# quadripod_2lm_nano.net
KiCad netlist of a schematic drawn in EAGLE
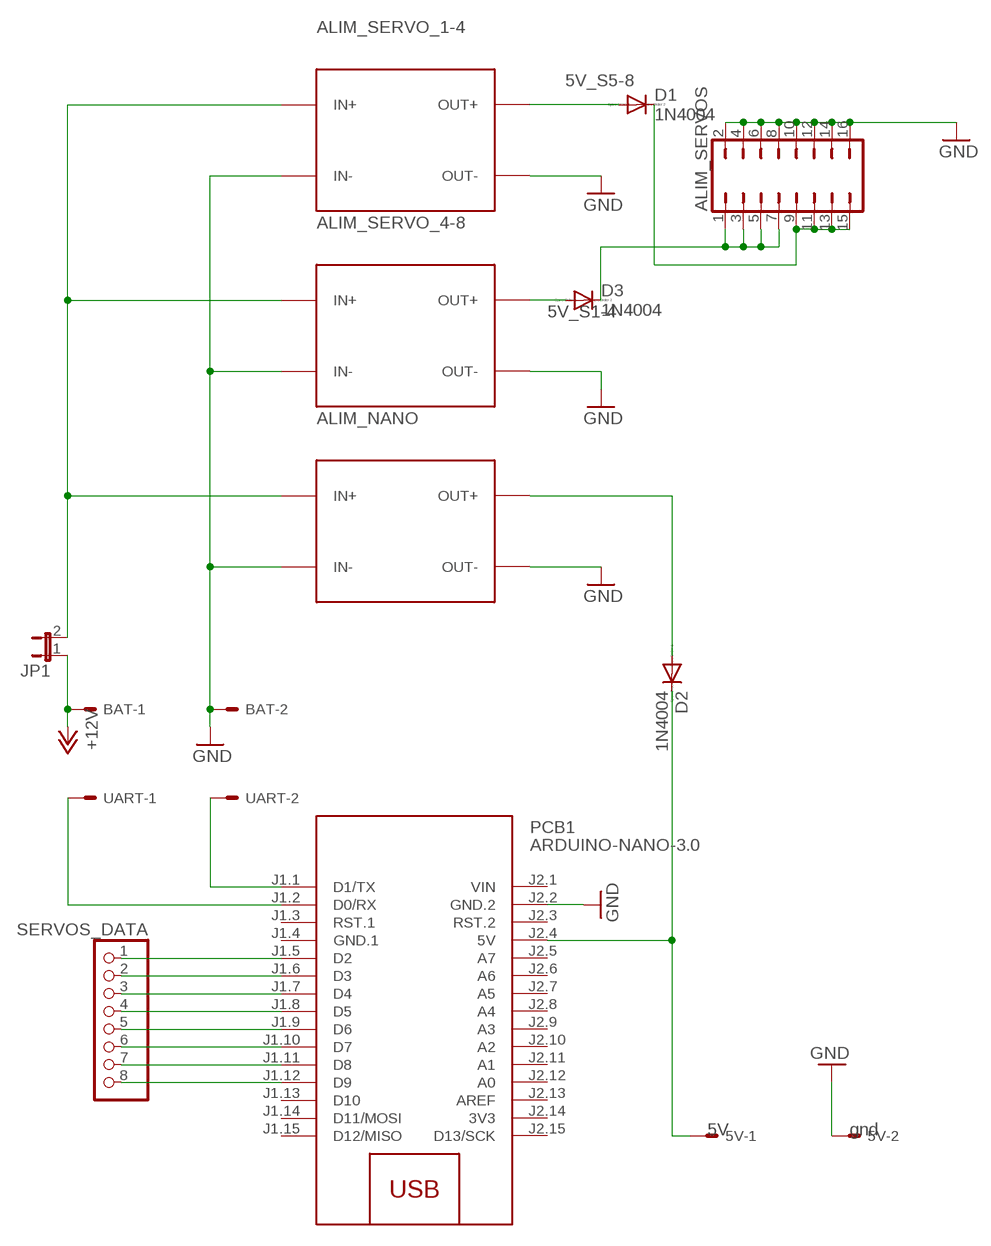
[diagram p0: schematic, sheet 1]

(export (version "E")
  (design (tool "Eeschema 10.0.6"))
  (components
    (comp (ref "5V")
      (value "332-02")
      (footprint "eagle-import:332-02")
      (fields (field (name "V") "5V") (field (name "VOLT") "gnd"))
      (libsource (lib "eagle-import") (part "332-02"))
    )
    (comp (ref "ALIM_NANO")
      (value "DC-DC-STEP-DOWN-LM2596")
      (footprint "eagle-import:DC-DC-STEP-DOWN-LM2596")
      (libsource (lib "eagle-import") (part "DC-DC-STEP-DOWN-LM2596"))
    )
    (comp (ref "ALIM_SERVOS")
      (value "JP8Q")
      (footprint "eagle-import:JP8Q")
      (libsource (lib "eagle-import") (part "JP8Q"))
    )
    (comp (ref "ALIM_SERVO_1-4")
      (value "DC-DC-STEP-DOWN-LM2596")
      (footprint "eagle-import:DC-DC-STEP-DOWN-LM2596")
      (libsource (lib "eagle-import") (part "DC-DC-STEP-DOWN-LM2596"))
    )
    (comp (ref "ALIM_SERVO_4-8")
      (value "DC-DC-STEP-DOWN-LM2596")
      (footprint "eagle-import:DC-DC-STEP-DOWN-LM2596")
      (libsource (lib "eagle-import") (part "DC-DC-STEP-DOWN-LM2596"))
    )
    (comp (ref "BAT")
      (value "332-02")
      (footprint "eagle-import:332-02")
      (fields (field (name "VOLTAGE") "12V") (field (name "VOLT") "gnd"))
      (libsource (lib "eagle-import") (part "332-02"))
    )
    (comp (ref "D1")
      (value "1N4004")
      (footprint "eagle-import:DO41-10")
      (libsource (lib "eagle-import") (part "1N4004"))
    )
    (comp (ref "D2")
      (value "1N4004")
      (footprint "eagle-import:DO41-10")
      (libsource (lib "eagle-import") (part "1N4004"))
    )
    (comp (ref "D3")
      (value "1N4004")
      (footprint "eagle-import:DO41-10")
      (libsource (lib "eagle-import") (part "1N4004"))
    )
    (comp (ref "JP1")
      (value "JP1E")
      (footprint "eagle-import:JP1")
      (libsource (lib "eagle-import") (part "JP1E"))
    )
    (comp (ref "PCB1")
      (value "ARDUINO-NANO-3.0")
      (footprint "eagle-import:ARDUINO-NANO-3.0")
      (libsource (lib "eagle-import") (part "ARDUINO-NANO-3.0"))
    )
    (comp (ref "SERVOS_DATA")
      (value "PINHD-1X8")
      (footprint "eagle-import:1X08")
      (libsource (lib "eagle-import") (part "PINHD-1X8"))
    )
    (comp (ref "UART")
      (value "332-02")
      (footprint "eagle-import:332-02")
      (libsource (lib "eagle-import") (part "332-02"))
    )
  )
  (nets
    (net (code "1") (name "+12V") (class "Default")
      (node (ref "BAT") (pin "1") (pinfunction "S_1") (pintype "passive"))
      (node (ref "JP1") (pin "1") (pinfunction "1_1") (pintype "passive"))
    )
    (net (code "2") (name "/3V3") (class "Default")
      (node (ref "PCB1") (pin "J2.14") (pinfunction "3V3_J2.14") (pintype "power_in"))
    )
    (net (code "3") (name "/5V_S1-4") (class "Default")
      (node (ref "ALIM_SERVOS") (pin "1") (pinfunction "1_1") (pintype "passive"))
      (node (ref "ALIM_SERVOS") (pin "3") (pinfunction "3_3") (pintype "passive"))
      (node (ref "ALIM_SERVOS") (pin "5") (pinfunction "5_5") (pintype "passive"))
      (node (ref "ALIM_SERVOS") (pin "7") (pinfunction "7_7") (pintype "passive"))
      (node (ref "D3") (pin "C") (pinfunction "C_C") (pintype "passive"))
    )
    (net (code "4") (name "/5V_S5-8") (class "Default")
      (node (ref "ALIM_SERVOS") (pin "11") (pinfunction "11_11") (pintype "passive"))
      (node (ref "ALIM_SERVOS") (pin "13") (pinfunction "13_13") (pintype "passive"))
      (node (ref "ALIM_SERVOS") (pin "15") (pinfunction "15_15") (pintype "passive"))
      (node (ref "ALIM_SERVOS") (pin "9") (pinfunction "9_9") (pintype "passive"))
      (node (ref "D1") (pin "C") (pinfunction "C_C") (pintype "passive"))
    )
    (net (code "5") (name "/GND.1") (class "Default")
      (node (ref "PCB1") (pin "J1.4") (pinfunction "GND.1_J1.4") (pintype "power_in"))
    )
    (net (code "6") (name "/VIN") (class "Default")
      (node (ref "PCB1") (pin "J2.1") (pinfunction "VIN_J2.1") (pintype "power_in"))
    )
    (net (code "7") (name "GND") (class "Default")
      (node (ref "5V") (pin "2") (pinfunction "S_2") (pintype "passive"))
      (node (ref "ALIM_NANO") (pin "IN-") (pinfunction "IN-_IN-") (pintype "bidirectional"))
      (node (ref "ALIM_NANO") (pin "OUT-") (pinfunction "OUT-_OUT-") (pintype "bidirectional"))
      (node (ref "ALIM_SERVOS") (pin "10") (pinfunction "10_10") (pintype "passive"))
      (node (ref "ALIM_SERVOS") (pin "12") (pinfunction "12_12") (pintype "passive"))
      (node (ref "ALIM_SERVOS") (pin "14") (pinfunction "14_14") (pintype "passive"))
      (node (ref "ALIM_SERVOS") (pin "16") (pinfunction "16_16") (pintype "passive"))
      (node (ref "ALIM_SERVOS") (pin "2") (pinfunction "2_2") (pintype "passive"))
      (node (ref "ALIM_SERVOS") (pin "4") (pinfunction "4_4") (pintype "passive"))
      (node (ref "ALIM_SERVOS") (pin "6") (pinfunction "6_6") (pintype "passive"))
      (node (ref "ALIM_SERVOS") (pin "8") (pinfunction "8_8") (pintype "passive"))
      (node (ref "ALIM_SERVO_1-4") (pin "IN-") (pinfunction "IN-_IN-") (pintype "bidirectional"))
      (node (ref "ALIM_SERVO_1-4") (pin "OUT-") (pinfunction "OUT-_OUT-") (pintype "bidirectional"))
      (node (ref "ALIM_SERVO_4-8") (pin "IN-") (pinfunction "IN-_IN-") (pintype "bidirectional"))
      (node (ref "ALIM_SERVO_4-8") (pin "OUT-") (pinfunction "OUT-_OUT-") (pintype "bidirectional"))
      (node (ref "BAT") (pin "2") (pinfunction "S_2") (pintype "passive"))
      (node (ref "PCB1") (pin "J2.2") (pinfunction "GND.2_J2.2") (pintype "power_in"))
    )
    (net (code "8") (name "Net-(5VA-S)") (class "Default")
      (node (ref "5V") (pin "1") (pinfunction "S_1") (pintype "passive"))
      (node (ref "D2") (pin "C") (pinfunction "C_C") (pintype "passive"))
      (node (ref "PCB1") (pin "J2.4") (pinfunction "5V_J2.4") (pintype "power_in"))
    )
    (net (code "9") (name "Net-(ALIM_NANO-PadIN+)") (class "Default")
      (node (ref "ALIM_NANO") (pin "IN+") (pinfunction "IN+_IN+") (pintype "bidirectional"))
      (node (ref "ALIM_SERVO_1-4") (pin "IN+") (pinfunction "IN+_IN+") (pintype "bidirectional"))
      (node (ref "ALIM_SERVO_4-8") (pin "IN+") (pinfunction "IN+_IN+") (pintype "bidirectional"))
      (node (ref "JP1") (pin "2") (pinfunction "2_2") (pintype "passive"))
    )
    (net (code "10") (name "Net-(ALIM_NANO-PadOUT+)") (class "Default")
      (node (ref "ALIM_NANO") (pin "OUT+") (pinfunction "OUT+_OUT+") (pintype "bidirectional"))
      (node (ref "D2") (pin "A") (pinfunction "A_A") (pintype "passive"))
    )
    (net (code "11") (name "Net-(ALIM_SERVO_1-4-PadOUT+)") (class "Default")
      (node (ref "ALIM_SERVO_1-4") (pin "OUT+") (pinfunction "OUT+_OUT+") (pintype "bidirectional"))
      (node (ref "D1") (pin "A") (pinfunction "A_A") (pintype "passive"))
    )
    (net (code "12") (name "Net-(ALIM_SERVO_4-8-PadOUT+)") (class "Default")
      (node (ref "ALIM_SERVO_4-8") (pin "OUT+") (pinfunction "OUT+_OUT+") (pintype "bidirectional"))
      (node (ref "D3") (pin "A") (pinfunction "A_A") (pintype "passive"))
    )
    (net (code "13") (name "Net-(PCB1-D0{slash}RX)") (class "Default")
      (node (ref "PCB1") (pin "J1.2") (pinfunction "D0/RX_J1.2") (pintype "bidirectional"))
      (node (ref "UART") (pin "1") (pinfunction "S_1") (pintype "passive"))
    )
    (net (code "14") (name "Net-(PCB1-D1{slash}TX)") (class "Default")
      (node (ref "PCB1") (pin "J1.1") (pinfunction "D1/TX_J1.1") (pintype "bidirectional"))
      (node (ref "UART") (pin "2") (pinfunction "S_2") (pintype "passive"))
    )
    (net (code "15") (name "Net-(PCB1-D2)") (class "Default")
      (node (ref "PCB1") (pin "J1.5") (pinfunction "D2_J1.5") (pintype "bidirectional"))
      (node (ref "SERVOS_DATA") (pin "1") (pinfunction "1_1") (pintype "passive"))
    )
    (net (code "16") (name "Net-(PCB1-D3)") (class "Default")
      (node (ref "PCB1") (pin "J1.6") (pinfunction "D3_J1.6") (pintype "bidirectional"))
      (node (ref "SERVOS_DATA") (pin "2") (pinfunction "2_2") (pintype "passive"))
    )
    (net (code "17") (name "Net-(PCB1-D4)") (class "Default")
      (node (ref "PCB1") (pin "J1.7") (pinfunction "D4_J1.7") (pintype "bidirectional"))
      (node (ref "SERVOS_DATA") (pin "3") (pinfunction "3_3") (pintype "passive"))
    )
    (net (code "18") (name "Net-(PCB1-D5)") (class "Default")
      (node (ref "PCB1") (pin "J1.8") (pinfunction "D5_J1.8") (pintype "bidirectional"))
      (node (ref "SERVOS_DATA") (pin "4") (pinfunction "4_4") (pintype "passive"))
    )
    (net (code "19") (name "Net-(PCB1-D6)") (class "Default")
      (node (ref "PCB1") (pin "J1.9") (pinfunction "D6_J1.9") (pintype "bidirectional"))
      (node (ref "SERVOS_DATA") (pin "5") (pinfunction "5_5") (pintype "passive"))
    )
    (net (code "20") (name "Net-(PCB1-D7)") (class "Default")
      (node (ref "PCB1") (pin "J1.10") (pinfunction "D7_J1.10") (pintype "bidirectional"))
      (node (ref "SERVOS_DATA") (pin "6") (pinfunction "6_6") (pintype "passive"))
    )
    (net (code "21") (name "Net-(PCB1-D8)") (class "Default")
      (node (ref "PCB1") (pin "J1.11") (pinfunction "D8_J1.11") (pintype "bidirectional"))
      (node (ref "SERVOS_DATA") (pin "7") (pinfunction "7_7") (pintype "passive"))
    )
    (net (code "22") (name "Net-(PCB1-D9)") (class "Default")
      (node (ref "PCB1") (pin "J1.12") (pinfunction "D9_J1.12") (pintype "bidirectional"))
      (node (ref "SERVOS_DATA") (pin "8") (pinfunction "8_8") (pintype "passive"))
    )
    (net (code "23") (name "unconnected-(PCB1-A0-PadJ2.12)") (class "Default")
      (node (ref "PCB1") (pin "J2.12") (pinfunction "A0_J2.12") (pintype "bidirectional"))
    )
    (net (code "24") (name "unconnected-(PCB1-A1-PadJ2.11)") (class "Default")
      (node (ref "PCB1") (pin "J2.11") (pinfunction "A1_J2.11") (pintype "bidirectional"))
    )
    (net (code "25") (name "unconnected-(PCB1-A2-PadJ2.10)") (class "Default")
      (node (ref "PCB1") (pin "J2.10") (pinfunction "A2_J2.10") (pintype "bidirectional"))
    )
    (net (code "26") (name "unconnected-(PCB1-A3-PadJ2.9)") (class "Default")
      (node (ref "PCB1") (pin "J2.9") (pinfunction "A3_J2.9") (pintype "bidirectional"))
    )
    (net (code "27") (name "unconnected-(PCB1-A4-PadJ2.8)") (class "Default")
      (node (ref "PCB1") (pin "J2.8") (pinfunction "A4_J2.8") (pintype "bidirectional"))
    )
    (net (code "28") (name "unconnected-(PCB1-A5-PadJ2.7)") (class "Default")
      (node (ref "PCB1") (pin "J2.7") (pinfunction "A5_J2.7") (pintype "bidirectional"))
    )
    (net (code "29") (name "unconnected-(PCB1-A6-PadJ2.6)") (class "Default")
      (node (ref "PCB1") (pin "J2.6") (pinfunction "A6_J2.6") (pintype "bidirectional"))
    )
    (net (code "30") (name "unconnected-(PCB1-A7-PadJ2.5)") (class "Default")
      (node (ref "PCB1") (pin "J2.5") (pinfunction "A7_J2.5") (pintype "bidirectional"))
    )
    (net (code "31") (name "unconnected-(PCB1-AREF-PadJ2.13)") (class "Default")
      (node (ref "PCB1") (pin "J2.13") (pinfunction "AREF_J2.13") (pintype "bidirectional"))
    )
    (net (code "32") (name "unconnected-(PCB1-D10-PadJ1.13)") (class "Default")
      (node (ref "PCB1") (pin "J1.13") (pinfunction "D10_J1.13") (pintype "bidirectional"))
    )
    (net (code "33") (name "unconnected-(PCB1-D11{slash}MOSI-PadJ1.14)") (class "Default")
      (node (ref "PCB1") (pin "J1.14") (pinfunction "D11/MOSI_J1.14") (pintype "bidirectional"))
    )
    (net (code "34") (name "unconnected-(PCB1-D12{slash}MISO-PadJ1.15)") (class "Default")
      (node (ref "PCB1") (pin "J1.15") (pinfunction "D12/MISO_J1.15") (pintype "bidirectional"))
    )
    (net (code "35") (name "unconnected-(PCB1-D13{slash}SCK-PadJ2.15)") (class "Default")
      (node (ref "PCB1") (pin "J2.15") (pinfunction "D13/SCK_J2.15") (pintype "bidirectional"))
    )
    (net (code "36") (name "unconnected-(PCB1-RST.1-PadJ1.3)") (class "Default")
      (node (ref "PCB1") (pin "J1.3") (pinfunction "RST.1_J1.3") (pintype "bidirectional"))
    )
    (net (code "37") (name "unconnected-(PCB1-RST.2-PadJ2.3)") (class "Default")
      (node (ref "PCB1") (pin "J2.3") (pinfunction "RST.2_J2.3") (pintype "bidirectional"))
    )
  )
)
